# debug-fpc.net
KiCad netlist of a schematic drawn in Altium Designer
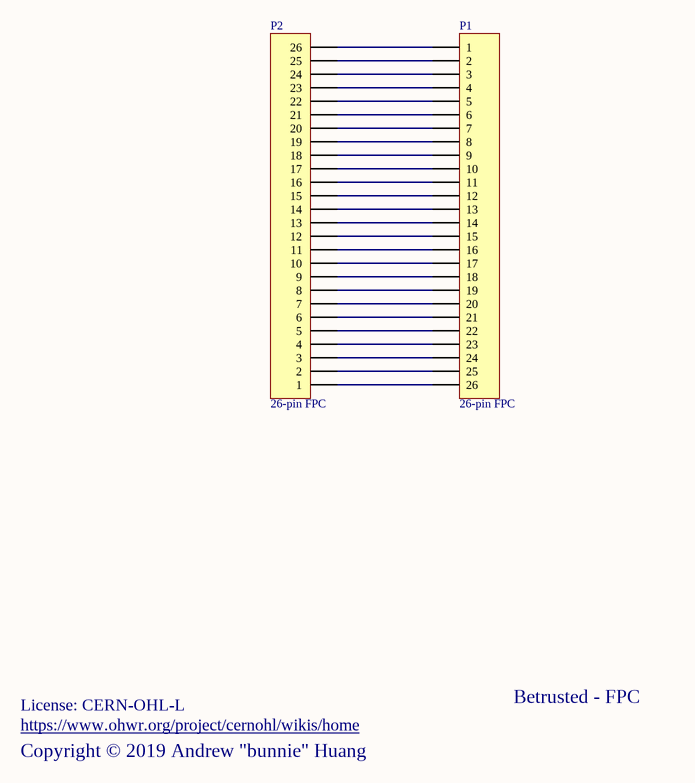
[diagram p0: debug-fpc.SchDoc]

(export (version "E")
  (design (tool "Eeschema 10.0.6"))
  (components
    (comp (ref "P1")
      (value "26-pin FPC")
      (footprint "HRS_FH34SRJ-26S-FPC")
      (description "26 Pin FPC footprint")
      (fields (field (name "MPN") "DNP"))
      (libsource (lib "commonsch-new") (part "FPC-26"))
    )
    (comp (ref "P2")
      (value "26-pin FPC")
      (footprint "HRS_FH34SRJ-26S-FPC")
      (description "26 Pin FPC footprint")
      (fields (field (name "MPN") "DNP"))
      (libsource (lib "") (part "FPC-26_1"))
    )
  )
  (nets
    (net (code "1") (name "Net-(P1-Pad1)") (class "Default")
      (node (ref "P1") (pin "1") (pinfunction "1_1") (pintype "passive"))
      (node (ref "P2") (pin "26") (pinfunction "26_26") (pintype "passive"))
    )
    (net (code "2") (name "Net-(P1-Pad2)") (class "Default")
      (node (ref "P1") (pin "2") (pinfunction "2_2") (pintype "passive"))
      (node (ref "P2") (pin "25") (pinfunction "25_25") (pintype "passive"))
    )
    (net (code "3") (name "Net-(P1-Pad3)") (class "Default")
      (node (ref "P1") (pin "3") (pinfunction "3_3") (pintype "passive"))
      (node (ref "P2") (pin "24") (pinfunction "24_24") (pintype "passive"))
    )
    (net (code "4") (name "Net-(P1-Pad4)") (class "Default")
      (node (ref "P1") (pin "4") (pinfunction "4_4") (pintype "passive"))
      (node (ref "P2") (pin "23") (pinfunction "23_23") (pintype "passive"))
    )
    (net (code "5") (name "Net-(P1-Pad5)") (class "Default")
      (node (ref "P1") (pin "5") (pinfunction "5_5") (pintype "passive"))
      (node (ref "P2") (pin "22") (pinfunction "22_22") (pintype "passive"))
    )
    (net (code "6") (name "Net-(P1-Pad6)") (class "Default")
      (node (ref "P1") (pin "6") (pinfunction "6_6") (pintype "passive"))
      (node (ref "P2") (pin "21") (pinfunction "21_21") (pintype "passive"))
    )
    (net (code "7") (name "Net-(P1-Pad7)") (class "Default")
      (node (ref "P1") (pin "7") (pinfunction "7_7") (pintype "passive"))
      (node (ref "P2") (pin "20") (pinfunction "20_20") (pintype "passive"))
    )
    (net (code "8") (name "Net-(P1-Pad8)") (class "Default")
      (node (ref "P1") (pin "8") (pinfunction "8_8") (pintype "passive"))
      (node (ref "P2") (pin "19") (pinfunction "19_19") (pintype "passive"))
    )
    (net (code "9") (name "Net-(P1-Pad9)") (class "Default")
      (node (ref "P1") (pin "9") (pinfunction "9_9") (pintype "passive"))
      (node (ref "P2") (pin "18") (pinfunction "18_18") (pintype "passive"))
    )
    (net (code "10") (name "Net-(P1-Pad10)") (class "Default")
      (node (ref "P1") (pin "10") (pinfunction "10_10") (pintype "passive"))
      (node (ref "P2") (pin "17") (pinfunction "17_17") (pintype "passive"))
    )
    (net (code "11") (name "Net-(P1-Pad11)") (class "Default")
      (node (ref "P1") (pin "11") (pinfunction "11_11") (pintype "passive"))
      (node (ref "P2") (pin "16") (pinfunction "16_16") (pintype "passive"))
    )
    (net (code "12") (name "Net-(P1-Pad12)") (class "Default")
      (node (ref "P1") (pin "12") (pinfunction "12_12") (pintype "passive"))
      (node (ref "P2") (pin "15") (pinfunction "15_15") (pintype "passive"))
    )
    (net (code "13") (name "Net-(P1-Pad13)") (class "Default")
      (node (ref "P1") (pin "13") (pinfunction "13_13") (pintype "passive"))
      (node (ref "P2") (pin "14") (pinfunction "14_14") (pintype "passive"))
    )
    (net (code "14") (name "Net-(P1-Pad14)") (class "Default")
      (node (ref "P1") (pin "14") (pinfunction "14_14") (pintype "passive"))
      (node (ref "P2") (pin "13") (pinfunction "13_13") (pintype "passive"))
    )
    (net (code "15") (name "Net-(P1-Pad15)") (class "Default")
      (node (ref "P1") (pin "15") (pinfunction "15_15") (pintype "passive"))
      (node (ref "P2") (pin "12") (pinfunction "12_12") (pintype "passive"))
    )
    (net (code "16") (name "Net-(P1-Pad16)") (class "Default")
      (node (ref "P1") (pin "16") (pinfunction "16_16") (pintype "passive"))
      (node (ref "P2") (pin "11") (pinfunction "11_11") (pintype "passive"))
    )
    (net (code "17") (name "Net-(P1-Pad17)") (class "Default")
      (node (ref "P1") (pin "17") (pinfunction "17_17") (pintype "passive"))
      (node (ref "P2") (pin "10") (pinfunction "10_10") (pintype "passive"))
    )
    (net (code "18") (name "Net-(P1-Pad18)") (class "Default")
      (node (ref "P1") (pin "18") (pinfunction "18_18") (pintype "passive"))
      (node (ref "P2") (pin "9") (pinfunction "9_9") (pintype "passive"))
    )
    (net (code "19") (name "Net-(P1-Pad19)") (class "Default")
      (node (ref "P1") (pin "19") (pinfunction "19_19") (pintype "passive"))
      (node (ref "P2") (pin "8") (pinfunction "8_8") (pintype "passive"))
    )
    (net (code "20") (name "Net-(P1-Pad20)") (class "Default")
      (node (ref "P1") (pin "20") (pinfunction "20_20") (pintype "passive"))
      (node (ref "P2") (pin "7") (pinfunction "7_7") (pintype "passive"))
    )
    (net (code "21") (name "Net-(P1-Pad21)") (class "Default")
      (node (ref "P1") (pin "21") (pinfunction "21_21") (pintype "passive"))
      (node (ref "P2") (pin "6") (pinfunction "6_6") (pintype "passive"))
    )
    (net (code "22") (name "Net-(P1-Pad22)") (class "Default")
      (node (ref "P1") (pin "22") (pinfunction "22_22") (pintype "passive"))
      (node (ref "P2") (pin "5") (pinfunction "5_5") (pintype "passive"))
    )
    (net (code "23") (name "Net-(P1-Pad23)") (class "Default")
      (node (ref "P1") (pin "23") (pinfunction "23_23") (pintype "passive"))
      (node (ref "P2") (pin "4") (pinfunction "4_4") (pintype "passive"))
    )
    (net (code "24") (name "Net-(P1-Pad24)") (class "Default")
      (node (ref "P1") (pin "24") (pinfunction "24_24") (pintype "passive"))
      (node (ref "P2") (pin "3") (pinfunction "3_3") (pintype "passive"))
    )
    (net (code "25") (name "Net-(P1-Pad25)") (class "Default")
      (node (ref "P1") (pin "25") (pinfunction "25_25") (pintype "passive"))
      (node (ref "P2") (pin "2") (pinfunction "2_2") (pintype "passive"))
    )
    (net (code "26") (name "Net-(P1-Pad26)") (class "Default")
      (node (ref "P1") (pin "26") (pinfunction "26_26") (pintype "passive"))
      (node (ref "P2") (pin "1") (pinfunction "1_1") (pintype "passive"))
    )
  )
)
